# PGTN_daisy2_main_12cvin.net
KiCad netlist of a schematic drawn in EAGLE
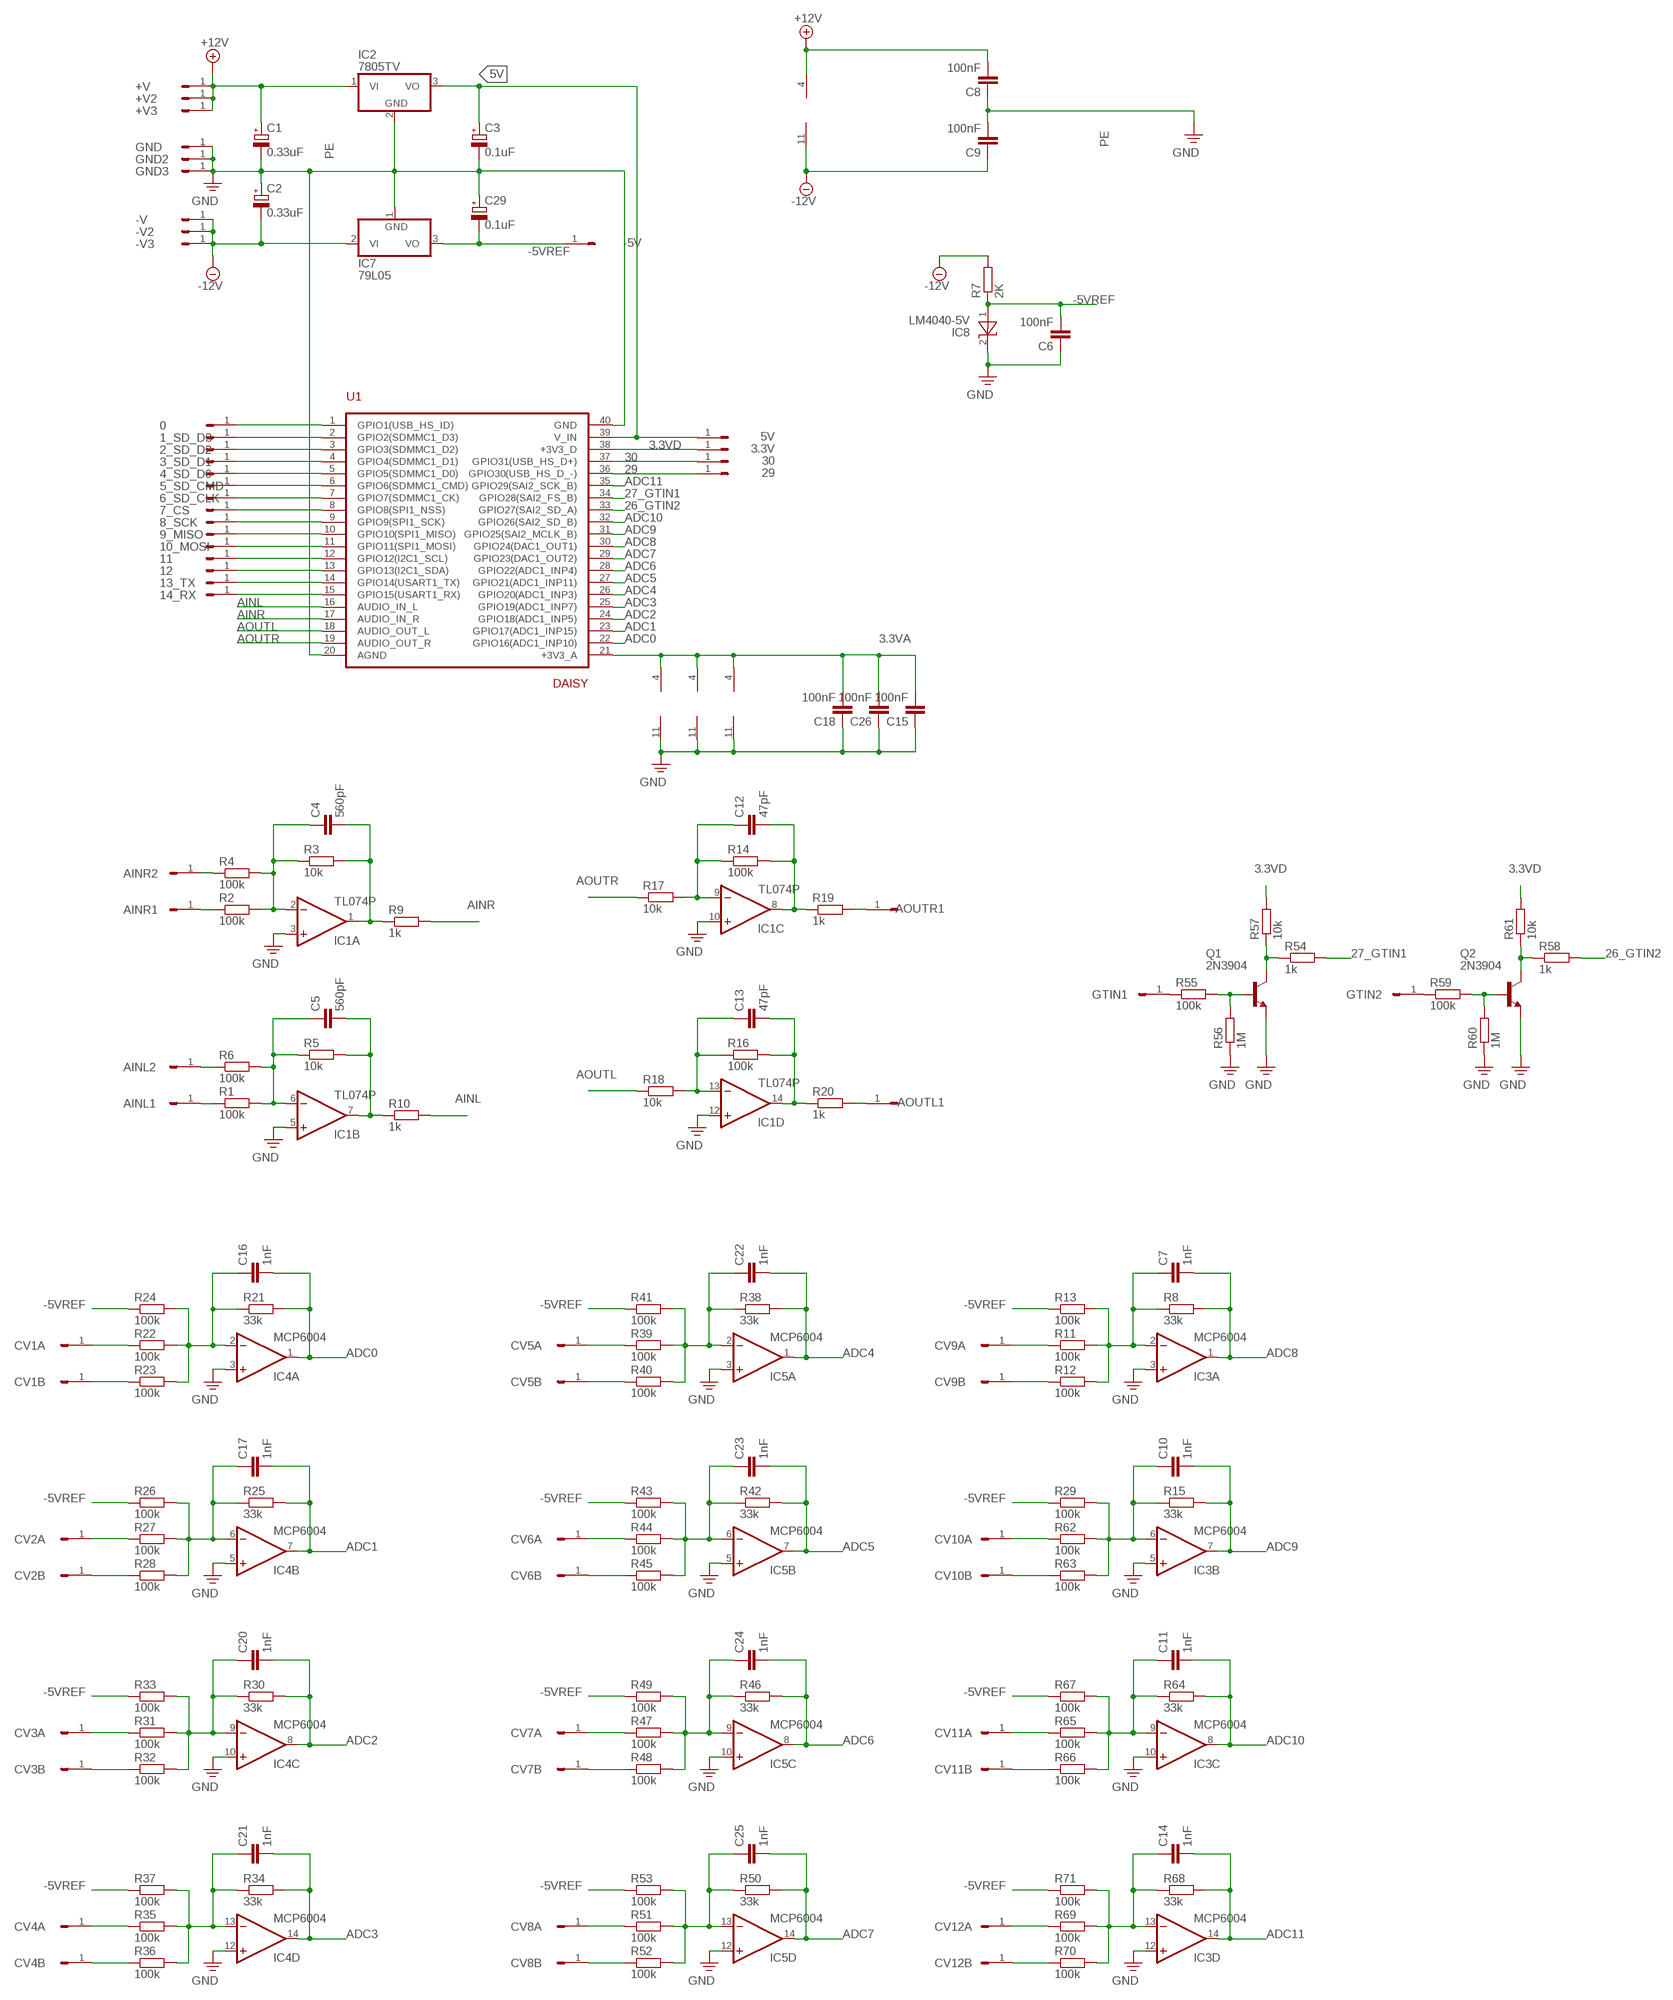
[diagram p0: schematic, sheet 1]

(export (version "E")
  (design (tool "Eeschema 10.0.6"))
  (components
    (comp (ref "+V")
      (value "HEADER/MALE/01")
      (footprint "eagle-import:HEADER_MALE_01")
      (fields (field (name "SPICEPREFIX") "X"))
      (libsource (lib "eagle-import") (part "HEADER/MALE/01"))
    )
    (comp (ref "+V2")
      (value "HEADER/MALE/01")
      (footprint "eagle-import:HEADER_MALE_01")
      (fields (field (name "SPICEPREFIX") "X"))
      (libsource (lib "eagle-import") (part "HEADER/MALE/01"))
    )
    (comp (ref "+V3")
      (value "HEADER/MALE/01")
      (footprint "eagle-import:HEADER_MALE_01")
      (fields (field (name "SPICEPREFIX") "X"))
      (libsource (lib "eagle-import") (part "HEADER/MALE/01"))
    )
    (comp (ref "-5V")
      (value "HEADER/MALE/01")
      (footprint "eagle-import:HEADER_MALE_01")
      (fields (field (name "SPICEPREFIX") "X"))
      (libsource (lib "eagle-import") (part "HEADER/MALE/01"))
    )
    (comp (ref "-V")
      (value "HEADER/MALE/01")
      (footprint "eagle-import:HEADER_MALE_01")
      (fields (field (name "SPICEPREFIX") "X"))
      (libsource (lib "eagle-import") (part "HEADER/MALE/01"))
    )
    (comp (ref "-V2")
      (value "HEADER/MALE/01")
      (footprint "eagle-import:HEADER_MALE_01")
      (fields (field (name "SPICEPREFIX") "X"))
      (libsource (lib "eagle-import") (part "HEADER/MALE/01"))
    )
    (comp (ref "-V3")
      (value "HEADER/MALE/01")
      (footprint "eagle-import:HEADER_MALE_01")
      (fields (field (name "SPICEPREFIX") "X"))
      (libsource (lib "eagle-import") (part "HEADER/MALE/01"))
    )
    (comp (ref "0")
      (value "HEADER/MALE/01")
      (footprint "eagle-import:HEADER_MALE_01")
      (fields (field (name "SPICEPREFIX") "X"))
      (libsource (lib "eagle-import") (part "HEADER/MALE/01"))
    )
    (comp (ref "1_SD_D3")
      (value "HEADER/MALE/01")
      (footprint "eagle-import:HEADER_MALE_01")
      (fields (field (name "SPICEPREFIX") "X"))
      (libsource (lib "eagle-import") (part "HEADER/MALE/01"))
    )
    (comp (ref "2_SD_D2")
      (value "HEADER/MALE/01")
      (footprint "eagle-import:HEADER_MALE_01")
      (fields (field (name "SPICEPREFIX") "X"))
      (libsource (lib "eagle-import") (part "HEADER/MALE/01"))
    )
    (comp (ref "3.3V")
      (value "HEADER/MALE/01")
      (footprint "eagle-import:HEADER_MALE_01")
      (fields (field (name "SPICEPREFIX") "X"))
      (libsource (lib "eagle-import") (part "HEADER/MALE/01"))
    )
    (comp (ref "3_SD_D1")
      (value "HEADER/MALE/01")
      (footprint "eagle-import:HEADER_MALE_01")
      (fields (field (name "SPICEPREFIX") "X"))
      (libsource (lib "eagle-import") (part "HEADER/MALE/01"))
    )
    (comp (ref "4_SD_D0")
      (value "HEADER/MALE/01")
      (footprint "eagle-import:HEADER_MALE_01")
      (fields (field (name "SPICEPREFIX") "X"))
      (libsource (lib "eagle-import") (part "HEADER/MALE/01"))
    )
    (comp (ref "5V")
      (value "HEADER/MALE/01")
      (footprint "eagle-import:HEADER_MALE_01")
      (fields (field (name "SPICEPREFIX") "X"))
      (libsource (lib "eagle-import") (part "HEADER/MALE/01"))
    )
    (comp (ref "5_SD_CMD")
      (value "HEADER/MALE/01")
      (footprint "eagle-import:HEADER_MALE_01")
      (fields (field (name "SPICEPREFIX") "X"))
      (libsource (lib "eagle-import") (part "HEADER/MALE/01"))
    )
    (comp (ref "6_SD_CLK")
      (value "HEADER/MALE/01")
      (footprint "eagle-import:HEADER_MALE_01")
      (fields (field (name "SPICEPREFIX") "X"))
      (libsource (lib "eagle-import") (part "HEADER/MALE/01"))
    )
    (comp (ref "7_CS")
      (value "HEADER/MALE/01")
      (footprint "eagle-import:HEADER_MALE_01")
      (fields (field (name "SPICEPREFIX") "X"))
      (libsource (lib "eagle-import") (part "HEADER/MALE/01"))
    )
    (comp (ref "8_SCK")
      (value "HEADER/MALE/01")
      (footprint "eagle-import:HEADER_MALE_01")
      (fields (field (name "SPICEPREFIX") "X"))
      (libsource (lib "eagle-import") (part "HEADER/MALE/01"))
    )
    (comp (ref "9_MISO")
      (value "HEADER/MALE/01")
      (footprint "eagle-import:HEADER_MALE_01")
      (fields (field (name "SPICEPREFIX") "X"))
      (libsource (lib "eagle-import") (part "HEADER/MALE/01"))
    )
    (comp (ref "10_MOSI")
      (value "HEADER/MALE/01")
      (footprint "eagle-import:HEADER_MALE_01")
      (fields (field (name "SPICEPREFIX") "X"))
      (libsource (lib "eagle-import") (part "HEADER/MALE/01"))
    )
    (comp (ref "11")
      (value "HEADER/MALE/01")
      (footprint "eagle-import:HEADER_MALE_01")
      (fields (field (name "SPICEPREFIX") "X"))
      (libsource (lib "eagle-import") (part "HEADER/MALE/01"))
    )
    (comp (ref "12")
      (value "HEADER/MALE/01")
      (footprint "eagle-import:HEADER_MALE_01")
      (fields (field (name "SPICEPREFIX") "X"))
      (libsource (lib "eagle-import") (part "HEADER/MALE/01"))
    )
    (comp (ref "13_TX")
      (value "HEADER/MALE/01")
      (footprint "eagle-import:HEADER_MALE_01")
      (fields (field (name "SPICEPREFIX") "X"))
      (libsource (lib "eagle-import") (part "HEADER/MALE/01"))
    )
    (comp (ref "14_RX")
      (value "HEADER/MALE/01")
      (footprint "eagle-import:HEADER_MALE_01")
      (fields (field (name "SPICEPREFIX") "X"))
      (libsource (lib "eagle-import") (part "HEADER/MALE/01"))
    )
    (comp (ref "29")
      (value "HEADER/MALE/01")
      (footprint "eagle-import:HEADER_MALE_01")
      (fields (field (name "SPICEPREFIX") "X"))
      (libsource (lib "eagle-import") (part "HEADER/MALE/01"))
    )
    (comp (ref "30")
      (value "HEADER/MALE/01")
      (footprint "eagle-import:HEADER_MALE_01")
      (fields (field (name "SPICEPREFIX") "X"))
      (libsource (lib "eagle-import") (part "HEADER/MALE/01"))
    )
    (comp (ref "AINL1")
      (value "HEADER/MALE/01")
      (footprint "eagle-import:HEADER_MALE_01")
      (fields (field (name "SPICEPREFIX") "X"))
      (libsource (lib "eagle-import") (part "HEADER/MALE/01"))
    )
    (comp (ref "AINL2")
      (value "HEADER/MALE/01")
      (footprint "eagle-import:HEADER_MALE_01")
      (fields (field (name "SPICEPREFIX") "X"))
      (libsource (lib "eagle-import") (part "HEADER/MALE/01"))
    )
    (comp (ref "AINR1")
      (value "HEADER/MALE/01")
      (footprint "eagle-import:HEADER_MALE_01")
      (fields (field (name "SPICEPREFIX") "X"))
      (libsource (lib "eagle-import") (part "HEADER/MALE/01"))
    )
    (comp (ref "AINR2")
      (value "HEADER/MALE/01")
      (footprint "eagle-import:HEADER_MALE_01")
      (fields (field (name "SPICEPREFIX") "X"))
      (libsource (lib "eagle-import") (part "HEADER/MALE/01"))
    )
    (comp (ref "AOUTL1")
      (value "HEADER/MALE/01")
      (footprint "eagle-import:HEADER_MALE_01")
      (fields (field (name "SPICEPREFIX") "X"))
      (libsource (lib "eagle-import") (part "HEADER/MALE/01"))
    )
    (comp (ref "AOUTR1")
      (value "HEADER/MALE/01")
      (footprint "eagle-import:HEADER_MALE_01")
      (fields (field (name "SPICEPREFIX") "X"))
      (libsource (lib "eagle-import") (part "HEADER/MALE/01"))
    )
    (comp (ref "C1")
      (value "0.33uF")
      (footprint "eagle-import:E2,5-6")
      (fields (field (name "SPICEPREFIX") "C"))
      (libsource (lib "eagle-import") (part "CAPACITOR/POLARIZEDE2.5-6"))
    )
    (comp (ref "C2")
      (value "0.33uF")
      (footprint "eagle-import:E2,5-6")
      (fields (field (name "SPICEPREFIX") "C"))
      (libsource (lib "eagle-import") (part "CAPACITOR/POLARIZEDE2.5-6"))
    )
    (comp (ref "C3")
      (value "0.1uF")
      (footprint "eagle-import:E2,5-6")
      (fields (field (name "SPICEPREFIX") "C"))
      (libsource (lib "eagle-import") (part "CAPACITOR/POLARIZEDE2.5-6"))
    )
    (comp (ref "C4")
      (value "560pF")
      (footprint "eagle-import:CERAMICDISC_5")
      (libsource (lib "eagle-import") (part "CAPACITORCERAMICDISC/5"))
    )
    (comp (ref "C5")
      (value "560pF")
      (footprint "eagle-import:CERAMICDISC_5")
      (libsource (lib "eagle-import") (part "CAPACITORCERAMICDISC/5"))
    )
    (comp (ref "C6")
      (value "100nF")
      (footprint "eagle-import:CERAMICDISC_5")
      (libsource (lib "eagle-import") (part "CAPACITORCERAMICDISC/5"))
    )
    (comp (ref "C7")
      (value "1nF")
      (footprint "eagle-import:CERAMICDISC_5")
      (libsource (lib "eagle-import") (part "CAPACITORCERAMICDISC/5"))
    )
    (comp (ref "C8")
      (value "100nF")
      (footprint "eagle-import:CERAMICDISC_5")
      (libsource (lib "eagle-import") (part "CAPACITORCERAMICDISC/5"))
    )
    (comp (ref "C9")
      (value "100nF")
      (footprint "eagle-import:CERAMICDISC_5")
      (libsource (lib "eagle-import") (part "CAPACITORCERAMICDISC/5"))
    )
    (comp (ref "C10")
      (value "1nF")
      (footprint "eagle-import:CERAMICDISC_5")
      (libsource (lib "eagle-import") (part "CAPACITORCERAMICDISC/5"))
    )
    (comp (ref "C11")
      (value "1nF")
      (footprint "eagle-import:CERAMICDISC_5")
      (libsource (lib "eagle-import") (part "CAPACITORCERAMICDISC/5"))
    )
    (comp (ref "C12")
      (value "47pF")
      (footprint "eagle-import:CERAMICDISC_5")
      (libsource (lib "eagle-import") (part "CAPACITORCERAMICDISC/5"))
    )
    (comp (ref "C13")
      (value "47pF")
      (footprint "eagle-import:CERAMICDISC_5")
      (libsource (lib "eagle-import") (part "CAPACITORCERAMICDISC/5"))
    )
    (comp (ref "C14")
      (value "1nF")
      (footprint "eagle-import:CERAMICDISC_5")
      (libsource (lib "eagle-import") (part "CAPACITORCERAMICDISC/5"))
    )
    (comp (ref "C15")
      (value "100nF")
      (footprint "eagle-import:CERAMICDISC_5")
      (libsource (lib "eagle-import") (part "CAPACITORCERAMICDISC/5"))
    )
    (comp (ref "C16")
      (value "1nF")
      (footprint "eagle-import:CERAMICDISC_5")
      (libsource (lib "eagle-import") (part "CAPACITORCERAMICDISC/5"))
    )
    (comp (ref "C17")
      (value "1nF")
      (footprint "eagle-import:CERAMICDISC_5")
      (libsource (lib "eagle-import") (part "CAPACITORCERAMICDISC/5"))
    )
    (comp (ref "C18")
      (value "100nF")
      (footprint "eagle-import:CERAMICDISC_5")
      (libsource (lib "eagle-import") (part "CAPACITORCERAMICDISC/5"))
    )
    (comp (ref "C20")
      (value "1nF")
      (footprint "eagle-import:CERAMICDISC_5")
      (libsource (lib "eagle-import") (part "CAPACITORCERAMICDISC/5"))
    )
    (comp (ref "C21")
      (value "1nF")
      (footprint "eagle-import:CERAMICDISC_5")
      (libsource (lib "eagle-import") (part "CAPACITORCERAMICDISC/5"))
    )
    (comp (ref "C22")
      (value "1nF")
      (footprint "eagle-import:CERAMICDISC_5")
      (libsource (lib "eagle-import") (part "CAPACITORCERAMICDISC/5"))
    )
    (comp (ref "C23")
      (value "1nF")
      (footprint "eagle-import:CERAMICDISC_5")
      (libsource (lib "eagle-import") (part "CAPACITORCERAMICDISC/5"))
    )
    (comp (ref "C24")
      (value "1nF")
      (footprint "eagle-import:CERAMICDISC_5")
      (libsource (lib "eagle-import") (part "CAPACITORCERAMICDISC/5"))
    )
    (comp (ref "C25")
      (value "1nF")
      (footprint "eagle-import:CERAMICDISC_5")
      (libsource (lib "eagle-import") (part "CAPACITORCERAMICDISC/5"))
    )
    (comp (ref "C26")
      (value "100nF")
      (footprint "eagle-import:CERAMICDISC_5")
      (libsource (lib "eagle-import") (part "CAPACITORCERAMICDISC/5"))
    )
    (comp (ref "C29")
      (value "0.1uF")
      (footprint "eagle-import:E2,5-6")
      (fields (field (name "SPICEPREFIX") "C"))
      (libsource (lib "eagle-import") (part "CAPACITOR/POLARIZEDE2.5-6"))
    )
    (comp (ref "CV1A")
      (value "HEADER/MALE/01")
      (footprint "eagle-import:HEADER_MALE_01")
      (fields (field (name "SPICEPREFIX") "X"))
      (libsource (lib "eagle-import") (part "HEADER/MALE/01"))
    )
    (comp (ref "CV1B")
      (value "HEADER/MALE/01")
      (footprint "eagle-import:HEADER_MALE_01")
      (fields (field (name "SPICEPREFIX") "X"))
      (libsource (lib "eagle-import") (part "HEADER/MALE/01"))
    )
    (comp (ref "CV2A")
      (value "HEADER/MALE/01")
      (footprint "eagle-import:HEADER_MALE_01")
      (fields (field (name "SPICEPREFIX") "X"))
      (libsource (lib "eagle-import") (part "HEADER/MALE/01"))
    )
    (comp (ref "CV2B")
      (value "HEADER/MALE/01")
      (footprint "eagle-import:HEADER_MALE_01")
      (fields (field (name "SPICEPREFIX") "X"))
      (libsource (lib "eagle-import") (part "HEADER/MALE/01"))
    )
    (comp (ref "CV3A")
      (value "HEADER/MALE/01")
      (footprint "eagle-import:HEADER_MALE_01")
      (fields (field (name "SPICEPREFIX") "X"))
      (libsource (lib "eagle-import") (part "HEADER/MALE/01"))
    )
    (comp (ref "CV3B")
      (value "HEADER/MALE/01")
      (footprint "eagle-import:HEADER_MALE_01")
      (fields (field (name "SPICEPREFIX") "X"))
      (libsource (lib "eagle-import") (part "HEADER/MALE/01"))
    )
    (comp (ref "CV4A")
      (value "HEADER/MALE/01")
      (footprint "eagle-import:HEADER_MALE_01")
      (fields (field (name "SPICEPREFIX") "X"))
      (libsource (lib "eagle-import") (part "HEADER/MALE/01"))
    )
    (comp (ref "CV4B")
      (value "HEADER/MALE/01")
      (footprint "eagle-import:HEADER_MALE_01")
      (fields (field (name "SPICEPREFIX") "X"))
      (libsource (lib "eagle-import") (part "HEADER/MALE/01"))
    )
    (comp (ref "CV5A")
      (value "HEADER/MALE/01")
      (footprint "eagle-import:HEADER_MALE_01")
      (fields (field (name "SPICEPREFIX") "X"))
      (libsource (lib "eagle-import") (part "HEADER/MALE/01"))
    )
    (comp (ref "CV5B")
      (value "HEADER/MALE/01")
      (footprint "eagle-import:HEADER_MALE_01")
      (fields (field (name "SPICEPREFIX") "X"))
      (libsource (lib "eagle-import") (part "HEADER/MALE/01"))
    )
    (comp (ref "CV6A")
      (value "HEADER/MALE/01")
      (footprint "eagle-import:HEADER_MALE_01")
      (fields (field (name "SPICEPREFIX") "X"))
      (libsource (lib "eagle-import") (part "HEADER/MALE/01"))
    )
    (comp (ref "CV6B")
      (value "HEADER/MALE/01")
      (footprint "eagle-import:HEADER_MALE_01")
      (fields (field (name "SPICEPREFIX") "X"))
      (libsource (lib "eagle-import") (part "HEADER/MALE/01"))
    )
    (comp (ref "CV7A")
      (value "HEADER/MALE/01")
      (footprint "eagle-import:HEADER_MALE_01")
      (fields (field (name "SPICEPREFIX") "X"))
      (libsource (lib "eagle-import") (part "HEADER/MALE/01"))
    )
    (comp (ref "CV7B")
      (value "HEADER/MALE/01")
      (footprint "eagle-import:HEADER_MALE_01")
      (fields (field (name "SPICEPREFIX") "X"))
      (libsource (lib "eagle-import") (part "HEADER/MALE/01"))
    )
    (comp (ref "CV8A")
      (value "HEADER/MALE/01")
      (footprint "eagle-import:HEADER_MALE_01")
      (fields (field (name "SPICEPREFIX") "X"))
      (libsource (lib "eagle-import") (part "HEADER/MALE/01"))
    )
    (comp (ref "CV8B")
      (value "HEADER/MALE/01")
      (footprint "eagle-import:HEADER_MALE_01")
      (fields (field (name "SPICEPREFIX") "X"))
      (libsource (lib "eagle-import") (part "HEADER/MALE/01"))
    )
    (comp (ref "CV9A")
      (value "HEADER/MALE/01")
      (footprint "eagle-import:HEADER_MALE_01")
      (fields (field (name "SPICEPREFIX") "X"))
      (libsource (lib "eagle-import") (part "HEADER/MALE/01"))
    )
    (comp (ref "CV9B")
      (value "HEADER/MALE/01")
      (footprint "eagle-import:HEADER_MALE_01")
      (fields (field (name "SPICEPREFIX") "X"))
      (libsource (lib "eagle-import") (part "HEADER/MALE/01"))
    )
    (comp (ref "CV10A")
      (value "HEADER/MALE/01")
      (footprint "eagle-import:HEADER_MALE_01")
      (fields (field (name "SPICEPREFIX") "X"))
      (libsource (lib "eagle-import") (part "HEADER/MALE/01"))
    )
    (comp (ref "CV10B")
      (value "HEADER/MALE/01")
      (footprint "eagle-import:HEADER_MALE_01")
      (fields (field (name "SPICEPREFIX") "X"))
      (libsource (lib "eagle-import") (part "HEADER/MALE/01"))
    )
    (comp (ref "CV11A")
      (value "HEADER/MALE/01")
      (footprint "eagle-import:HEADER_MALE_01")
      (fields (field (name "SPICEPREFIX") "X"))
      (libsource (lib "eagle-import") (part "HEADER/MALE/01"))
    )
    (comp (ref "CV11B")
      (value "HEADER/MALE/01")
      (footprint "eagle-import:HEADER_MALE_01")
      (fields (field (name "SPICEPREFIX") "X"))
      (libsource (lib "eagle-import") (part "HEADER/MALE/01"))
    )
    (comp (ref "CV12A")
      (value "HEADER/MALE/01")
      (footprint "eagle-import:HEADER_MALE_01")
      (fields (field (name "SPICEPREFIX") "X"))
      (libsource (lib "eagle-import") (part "HEADER/MALE/01"))
    )
    (comp (ref "CV12B")
      (value "HEADER/MALE/01")
      (footprint "eagle-import:HEADER_MALE_01")
      (fields (field (name "SPICEPREFIX") "X"))
      (libsource (lib "eagle-import") (part "HEADER/MALE/01"))
    )
    (comp (ref "GND")
      (value "HEADER/MALE/01")
      (footprint "eagle-import:HEADER_MALE_01")
      (fields (field (name "SPICEPREFIX") "X"))
      (libsource (lib "eagle-import") (part "HEADER/MALE/01"))
    )
    (comp (ref "GND2")
      (value "HEADER/MALE/01")
      (footprint "eagle-import:HEADER_MALE_01")
      (fields (field (name "SPICEPREFIX") "X"))
      (libsource (lib "eagle-import") (part "HEADER/MALE/01"))
    )
    (comp (ref "GND3")
      (value "HEADER/MALE/01")
      (footprint "eagle-import:HEADER_MALE_01")
      (fields (field (name "SPICEPREFIX") "X"))
      (libsource (lib "eagle-import") (part "HEADER/MALE/01"))
    )
    (comp (ref "GTIN1")
      (value "HEADER/MALE/01")
      (footprint "eagle-import:HEADER_MALE_01")
      (fields (field (name "SPICEPREFIX") "X"))
      (libsource (lib "eagle-import") (part "HEADER/MALE/01"))
    )
    (comp (ref "GTIN2")
      (value "HEADER/MALE/01")
      (footprint "eagle-import:HEADER_MALE_01")
      (fields (field (name "SPICEPREFIX") "X"))
      (libsource (lib "eagle-import") (part "HEADER/MALE/01"))
    )
    (comp (ref "IC1")
      (value "TL074P")
      (footprint "eagle-import:DIL14")
      (libsource (lib "eagle-import") (part "TL074P"))
    )
    (comp (ref "IC2")
      (value "7805TV")
      (footprint "eagle-import:TO220V")
      (libsource (lib "eagle-import") (part "78TV05"))
    )
    (comp (ref "IC3")
      (value "MCP6004")
      (footprint "eagle-import:DIL14")
      (libsource (lib "eagle-import") (part "TL074P"))
    )
    (comp (ref "IC4")
      (value "MCP6004")
      (footprint "eagle-import:DIL14")
      (libsource (lib "eagle-import") (part "TL074P"))
    )
    (comp (ref "IC5")
      (value "MCP6004")
      (footprint "eagle-import:DIL14")
      (libsource (lib "eagle-import") (part "TL074P"))
    )
    (comp (ref "IC7")
      (value "79L05")
      (footprint "eagle-import:TO92")
      (libsource (lib "eagle-import") (part "79ZL05"))
    )
    (comp (ref "IC8")
      (value "LM4040-5V")
      (footprint "eagle-import:TO92")
      (libsource (lib "eagle-import") (part "LM4040"))
    )
    (comp (ref "Q1")
      (value "2N3904")
      (footprint "eagle-import:TO92")
      (libsource (lib "eagle-import") (part "2N3904"))
    )
    (comp (ref "Q2")
      (value "2N3904")
      (footprint "eagle-import:TO92")
      (libsource (lib "eagle-import") (part "2N3904"))
    )
    (comp (ref "R1")
      (value "100k")
      (footprint "eagle-import:RESISTOR_7.5")
      (libsource (lib "eagle-import") (part "RESISTORRESISTOR/UPRIGHT/7.5"))
    )
    (comp (ref "R2")
      (value "100k")
      (footprint "eagle-import:RESISTOR_7.5")
      (libsource (lib "eagle-import") (part "RESISTORRESISTOR/UPRIGHT/7.5"))
    )
    (comp (ref "R3")
      (value "10k")
      (footprint "eagle-import:RESISTOR_7.5")
      (libsource (lib "eagle-import") (part "RESISTORRESISTOR/UPRIGHT/7.5"))
    )
    (comp (ref "R4")
      (value "100k")
      (footprint "eagle-import:RESISTOR_7.5")
      (libsource (lib "eagle-import") (part "RESISTORRESISTOR/UPRIGHT/7.5"))
    )
    (comp (ref "R5")
      (value "10k")
      (footprint "eagle-import:RESISTOR_7.5")
      (libsource (lib "eagle-import") (part "RESISTORRESISTOR/UPRIGHT/7.5"))
    )
    (comp (ref "R6")
      (value "100k")
      (footprint "eagle-import:RESISTOR_7.5")
      (libsource (lib "eagle-import") (part "RESISTORRESISTOR/UPRIGHT/7.5"))
    )
    (comp (ref "R7")
      (value "2K")
      (footprint "eagle-import:RESISTOR_7.5")
      (libsource (lib "eagle-import") (part "RESISTORRESISTOR/UPRIGHT/7.5"))
    )
    (comp (ref "R8")
      (value "33k")
      (footprint "eagle-import:RESISTOR_7.5")
      (libsource (lib "eagle-import") (part "RESISTORRESISTOR/UPRIGHT/7.5"))
    )
    (comp (ref "R9")
      (value "1k")
      (footprint "eagle-import:RESISTOR_7.5")
      (libsource (lib "eagle-import") (part "RESISTORRESISTOR/UPRIGHT/7.5"))
    )
    (comp (ref "R10")
      (value "1k")
      (footprint "eagle-import:RESISTOR_7.5")
      (libsource (lib "eagle-import") (part "RESISTORRESISTOR/UPRIGHT/7.5"))
    )
    (comp (ref "R11")
      (value "100k")
      (footprint "eagle-import:RESISTOR_7.5")
      (libsource (lib "eagle-import") (part "RESISTORRESISTOR/UPRIGHT/7.5"))
    )
    (comp (ref "R12")
      (value "100k")
      (footprint "eagle-import:RESISTOR_7.5")
      (libsource (lib "eagle-import") (part "RESISTORRESISTOR/UPRIGHT/7.5"))
    )
    (comp (ref "R13")
      (value "100k")
      (footprint "eagle-import:RESISTOR_7.5")
      (libsource (lib "eagle-import") (part "RESISTORRESISTOR/UPRIGHT/7.5"))
    )
    (comp (ref "R14")
      (value "100k")
      (footprint "eagle-import:RESISTOR_7.5")
      (libsource (lib "eagle-import") (part "RESISTORRESISTOR/UPRIGHT/7.5"))
    )
    (comp (ref "R15")
      (value "33k")
      (footprint "eagle-import:RESISTOR_7.5")
      (libsource (lib "eagle-import") (part "RESISTORRESISTOR/UPRIGHT/7.5"))
    )
    (comp (ref "R16")
      (value "100k")
      (footprint "eagle-import:RESISTOR_7.5")
      (libsource (lib "eagle-import") (part "RESISTORRESISTOR/UPRIGHT/7.5"))
    )
    (comp (ref "R17")
      (value "10k")
      (footprint "eagle-import:RESISTOR_7.5")
      (libsource (lib "eagle-import") (part "RESISTORRESISTOR/UPRIGHT/7.5"))
    )
    (comp (ref "R18")
      (value "10k")
      (footprint "eagle-import:RESISTOR_7.5")
      (libsource (lib "eagle-import") (part "RESISTORRESISTOR/UPRIGHT/7.5"))
    )
    (comp (ref "R19")
      (value "1k")
      (footprint "eagle-import:RESISTOR_7.5")
      (libsource (lib "eagle-import") (part "RESISTORRESISTOR/UPRIGHT/7.5"))
    )
    (comp (ref "R20")
      (value "1k")
      (footprint "eagle-import:RESISTOR_7.5")
      (libsource (lib "eagle-import") (part "RESISTORRESISTOR/UPRIGHT/7.5"))
    )
    (comp (ref "R21")
      (value "33k")
      (footprint "eagle-import:RESISTOR_7.5")
      (libsource (lib "eagle-import") (part "RESISTORRESISTOR/UPRIGHT/7.5"))
    )
    (comp (ref "R22")
      (value "100k")
      (footprint "eagle-import:RESISTOR_7.5")
      (libsource (lib "eagle-import") (part "RESISTORRESISTOR/UPRIGHT/7.5"))
    )
    (comp (ref "R23")
      (value "100k")
      (footprint "eagle-import:RESISTOR_7.5")
      (libsource (lib "eagle-import") (part "RESISTORRESISTOR/UPRIGHT/7.5"))
    )
    (comp (ref "R24")
      (value "100k")
      (footprint "eagle-import:RESISTOR_7.5")
      (libsource (lib "eagle-import") (part "RESISTORRESISTOR/UPRIGHT/7.5"))
    )
    (comp (ref "R25")
      (value "33k")
      (footprint "eagle-import:RESISTOR_7.5")
      (libsource (lib "eagle-import") (part "RESISTORRESISTOR/UPRIGHT/7.5"))
    )
    (comp (ref "R26")
      (value "100k")
      (footprint "eagle-import:RESISTOR_7.5")
      (libsource (lib "eagle-import") (part "RESISTORRESISTOR/UPRIGHT/7.5"))
    )
    (comp (ref "R27")
      (value "100k")
      (footprint "eagle-import:RESISTOR_7.5")
      (libsource (lib "eagle-import") (part "RESISTORRESISTOR/UPRIGHT/7.5"))
    )
    (comp (ref "R28")
      (value "100k")
      (footprint "eagle-import:RESISTOR_7.5")
      (libsource (lib "eagle-import") (part "RESISTORRESISTOR/UPRIGHT/7.5"))
    )
    (comp (ref "R29")
      (value "100k")
      (footprint "eagle-import:RESISTOR_7.5")
      (libsource (lib "eagle-import") (part "RESISTORRESISTOR/UPRIGHT/7.5"))
    )
    (comp (ref "R30")
      (value "33k")
      (footprint "eagle-import:RESISTOR_7.5")
      (libsource (lib "eagle-import") (part "RESISTORRESISTOR/UPRIGHT/7.5"))
    )
    (comp (ref "R31")
      (value "100k")
      (footprint "eagle-import:RESISTOR_7.5")
      (libsource (lib "eagle-import") (part "RESISTORRESISTOR/UPRIGHT/7.5"))
    )
    (comp (ref "R32")
      (value "100k")
      (footprint "eagle-import:RESISTOR_7.5")
      (libsource (lib "eagle-import") (part "RESISTORRESISTOR/UPRIGHT/7.5"))
    )
    (comp (ref "R33")
      (value "100k")
      (footprint "eagle-import:RESISTOR_7.5")
      (libsource (lib "eagle-import") (part "RESISTORRESISTOR/UPRIGHT/7.5"))
    )
    (comp (ref "R34")
      (value "33k")
      (footprint "eagle-import:RESISTOR_7.5")
      (libsource (lib "eagle-import") (part "RESISTORRESISTOR/UPRIGHT/7.5"))
    )
    (comp (ref "R35")
      (value "100k")
      (footprint "eagle-import:RESISTOR_7.5")
      (libsource (lib "eagle-import") (part "RESISTORRESISTOR/UPRIGHT/7.5"))
    )
    (comp (ref "R36")
      (value "100k")
      (footprint "eagle-import:RESISTOR_7.5")
      (libsource (lib "eagle-import") (part "RESISTORRESISTOR/UPRIGHT/7.5"))
    )
    (comp (ref "R37")
      (value "100k")
      (footprint "eagle-import:RESISTOR_7.5")
      (libsource (lib "eagle-import") (part "RESISTORRESISTOR/UPRIGHT/7.5"))
    )
    (comp (ref "R38")
      (value "33k")
      (footprint "eagle-import:RESISTOR_7.5")
      (libsource (lib "eagle-import") (part "RESISTORRESISTOR/UPRIGHT/7.5"))
    )
    (comp (ref "R39")
      (value "100k")
      (footprint "eagle-import:RESISTOR_7.5")
      (libsource (lib "eagle-import") (part "RESISTORRESISTOR/UPRIGHT/7.5"))
    )
    (comp (ref "R40")
      (value "100k")
      (footprint "eagle-import:RESISTOR_7.5")
      (libsource (lib "eagle-import") (part "RESISTORRESISTOR/UPRIGHT/7.5"))
    )
    (comp (ref "R41")
      (value "100k")
      (footprint "eagle-import:RESISTOR_7.5")
      (libsource (lib "eagle-import") (part "RESISTORRESISTOR/UPRIGHT/7.5"))
    )
    (comp (ref "R42")
      (value "33k")
      (footprint "eagle-import:RESISTOR_7.5")
      (libsource (lib "eagle-import") (part "RESISTORRESISTOR/UPRIGHT/7.5"))
    )
    (comp (ref "R43")
      (value "100k")
      (footprint "eagle-import:RESISTOR_7.5")
      (libsource (lib "eagle-import") (part "RESISTORRESISTOR/UPRIGHT/7.5"))
    )
    (comp (ref "R44")
      (value "100k")
      (footprint "eagle-import:RESISTOR_7.5")
      (libsource (lib "eagle-import") (part "RESISTORRESISTOR/UPRIGHT/7.5"))
    )
    (comp (ref "R45")
      (value "100k")
      (footprint "eagle-import:RESISTOR_7.5")
      (libsource (lib "eagle-import") (part "RESISTORRESISTOR/UPRIGHT/7.5"))
    )
    (comp (ref "R46")
      (value "33k")
      (footprint "eagle-import:RESISTOR_7.5")
      (libsource (lib "eagle-import") (part "RESISTORRESISTOR/UPRIGHT/7.5"))
    )
    (comp (ref "R47")
      (value "100k")
      (footprint "eagle-import:RESISTOR_7.5")
      (libsource (lib "eagle-import") (part "RESISTORRESISTOR/UPRIGHT/7.5"))
    )
    (comp (ref "R48")
      (value "100k")
      (footprint "eagle-import:RESISTOR_7.5")
      (libsource (lib "eagle-import") (part "RESISTORRESISTOR/UPRIGHT/7.5"))
    )
    (comp (ref "R49")
      (value "100k")
      (footprint "eagle-import:RESISTOR_7.5")
      (libsource (lib "eagle-import") (part "RESISTORRESISTOR/UPRIGHT/7.5"))
    )
    (comp (ref "R50")
      (value "33k")
      (footprint "eagle-import:RESISTOR_7.5")
      (libsource (lib "eagle-import") (part "RESISTORRESISTOR/UPRIGHT/7.5"))
    )
    (comp (ref "R51")
      (value "100k")
      (footprint "eagle-import:RESISTOR_7.5")
      (libsource (lib "eagle-import") (part "RESISTORRESISTOR/UPRIGHT/7.5"))
    )
    (comp (ref "R52")
      (value "100k")
      (footprint "eagle-import:RESISTOR_7.5")
      (libsource (lib "eagle-import") (part "RESISTORRESISTOR/UPRIGHT/7.5"))
    )
    (comp (ref "R53")
      (value "100k")
      (footprint "eagle-import:RESISTOR_7.5")
      (libsource (lib "eagle-import") (part "RESISTORRESISTOR/UPRIGHT/7.5"))
    )
    (comp (ref "R54")
      (value "1k")
      (footprint "eagle-import:RESISTOR_7.5")
      (libsource (lib "eagle-import") (part "RESISTORRESISTOR/UPRIGHT/7.5"))
    )
    (comp (ref "R55")
      (value "100k")
      (footprint "eagle-import:RESISTOR_7.5")
      (libsource (lib "eagle-import") (part "RESISTORRESISTOR/UPRIGHT/7.5"))
    )
    (comp (ref "R56")
      (value "1M")
      (footprint "eagle-import:RESISTOR_7.5")
      (libsource (lib "eagle-import") (part "RESISTORRESISTOR/UPRIGHT/7.5"))
    )
    (comp (ref "R57")
      (value "10k")
      (footprint "eagle-import:RESISTOR_7.5")
      (libsource (lib "eagle-import") (part "RESISTORRESISTOR/UPRIGHT/7.5"))
    )
    (comp (ref "R58")
      (value "1k")
      (footprint "eagle-import:RESISTOR_7.5")
      (libsource (lib "eagle-import") (part "RESISTORRESISTOR/UPRIGHT/7.5"))
    )
    (comp (ref "R59")
      (value "100k")
      (footprint "eagle-import:RESISTOR_7.5")
      (libsource (lib "eagle-import") (part "RESISTORRESISTOR/UPRIGHT/7.5"))
    )
    (comp (ref "R60")
      (value "1M")
      (footprint "eagle-import:RESISTOR_7.5")
      (libsource (lib "eagle-import") (part "RESISTORRESISTOR/UPRIGHT/7.5"))
    )
    (comp (ref "R61")
      (value "10k")
      (footprint "eagle-import:RESISTOR_7.5")
      (libsource (lib "eagle-import") (part "RESISTORRESISTOR/UPRIGHT/7.5"))
    )
    (comp (ref "R62")
      (value "100k")
      (footprint "eagle-import:RESISTOR_7.5")
      (libsource (lib "eagle-import") (part "RESISTORRESISTOR/UPRIGHT/7.5"))
    )
    (comp (ref "R63")
      (value "100k")
      (footprint "eagle-import:RESISTOR_7.5")
      (libsource (lib "eagle-import") (part "RESISTORRESISTOR/UPRIGHT/7.5"))
    )
    (comp (ref "R64")
      (value "33k")
      (footprint "eagle-import:RESISTOR_7.5")
      (libsource (lib "eagle-import") (part "RESISTORRESISTOR/UPRIGHT/7.5"))
    )
    (comp (ref "R65")
      (value "100k")
      (footprint "eagle-import:RESISTOR_7.5")
      (libsource (lib "eagle-import") (part "RESISTORRESISTOR/UPRIGHT/7.5"))
    )
    (comp (ref "R66")
      (value "100k")
      (footprint "eagle-import:RESISTOR_7.5")
      (libsource (lib "eagle-import") (part "RESISTORRESISTOR/UPRIGHT/7.5"))
    )
    (comp (ref "R67")
      (value "100k")
      (footprint "eagle-import:RESISTOR_7.5")
      (libsource (lib "eagle-import") (part "RESISTORRESISTOR/UPRIGHT/7.5"))
    )
    (comp (ref "R68")
      (value "33k")
      (footprint "eagle-import:RESISTOR_7.5")
      (libsource (lib "eagle-import") (part "RESISTORRESISTOR/UPRIGHT/7.5"))
    )
    (comp (ref "R69")
      (value "100k")
      (footprint "eagle-import:RESISTOR_7.5")
      (libsource (lib "eagle-import") (part "RESISTORRESISTOR/UPRIGHT/7.5"))
    )
    (comp (ref "R70")
      (value "100k")
      (footprint "eagle-import:RESISTOR_7.5")
      (libsource (lib "eagle-import") (part "RESISTORRESISTOR/UPRIGHT/7.5"))
    )
    (comp (ref "R71")
      (value "100k")
      (footprint "eagle-import:RESISTOR_7.5")
      (libsource (lib "eagle-import") (part "RESISTORRESISTOR/UPRIGHT/7.5"))
    )
    (comp (ref "U1")
      (value "DAISY")
      (footprint "eagle-import:ES_DAISY_SEED")
      (libsource (lib "eagle-import") (part "ES_DAISY_SEED_REV4"))
    )
  )
  (nets
    (net (code "1") (name "+12V") (class "Default")
      (node (ref "+V") (pin "1") (pinfunction "3_1") (pintype "passive"))
      (node (ref "+V2") (pin "1") (pinfunction "3_1") (pintype "passive"))
      (node (ref "+V3") (pin "1") (pinfunction "3_1") (pintype "passive"))
      (node (ref "C1") (pin "+") (pinfunction "+_+") (pintype "passive"))
      (node (ref "C8") (pin "2") (pinfunction "2_2") (pintype "passive"))
      (node (ref "IC1") (pin "4") (pinfunction "V+_4") (pintype "power_in"))
      (node (ref "IC2") (pin "1") (pinfunction "VI_1") (pintype "input"))
    )
    (net (code "2") (name "-12V") (class "Default")
      (node (ref "-V") (pin "1") (pinfunction "3_1") (pintype "passive"))
      (node (ref "-V2") (pin "1") (pinfunction "3_1") (pintype "passive"))
      (node (ref "-V3") (pin "1") (pinfunction "3_1") (pintype "passive"))
      (node (ref "C2") (pin "-") (pinfunction "-_-") (pintype "passive"))
      (node (ref "C9") (pin "1") (pinfunction "1_1") (pintype "passive"))
      (node (ref "IC1") (pin "11") (pinfunction "V-_11") (pintype "power_in"))
      (node (ref "IC7") (pin "2") (pinfunction "VI_2") (pintype "input"))
      (node (ref "R7") (pin "2") (pinfunction "2_2") (pintype "passive"))
    )
    (net (code "3") (name "/-5VREF") (class "Default")
      (node (ref "-5V") (pin "1") (pinfunction "3_1") (pintype "passive"))
      (node (ref "C29") (pin "-") (pinfunction "-_-") (pintype "passive"))
      (node (ref "C6") (pin "2") (pinfunction "2_2") (pintype "passive"))
      (node (ref "IC7") (pin "3") (pinfunction "VO_3") (pintype "passive"))
      (node (ref "IC8") (pin "1") (pinfunction "A_1") (pintype "output"))
      (node (ref "R13") (pin "1") (pinfunction "1_1") (pintype "passive"))
      (node (ref "R24") (pin "1") (pinfunction "1_1") (pintype "passive"))
      (node (ref "R26") (pin "1") (pinfunction "1_1") (pintype "passive"))
      (node (ref "R29") (pin "1") (pinfunction "1_1") (pintype "passive"))
      (node (ref "R33") (pin "1") (pinfunction "1_1") (pintype "passive"))
      (node (ref "R37") (pin "1") (pinfunction "1_1") (pintype "passive"))
      (node (ref "R41") (pin "1") (pinfunction "1_1") (pintype "passive"))
      (node (ref "R43") (pin "1") (pinfunction "1_1") (pintype "passive"))
      (node (ref "R49") (pin "1") (pinfunction "1_1") (pintype "passive"))
      (node (ref "R53") (pin "1") (pinfunction "1_1") (pintype "passive"))
      (node (ref "R67") (pin "1") (pinfunction "1_1") (pintype "passive"))
      (node (ref "R7") (pin "1") (pinfunction "1_1") (pintype "passive"))
      (node (ref "R71") (pin "1") (pinfunction "1_1") (pintype "passive"))
    )
    (net (code "4") (name "/3.3VA") (class "Default")
      (node (ref "C15") (pin "2") (pinfunction "2_2") (pintype "passive"))
      (node (ref "C18") (pin "2") (pinfunction "2_2") (pintype "passive"))
      (node (ref "C26") (pin "2") (pinfunction "2_2") (pintype "passive"))
      (node (ref "IC3") (pin "4") (pinfunction "V+_4") (pintype "power_in"))
      (node (ref "IC4") (pin "4") (pinfunction "V+_4") (pintype "power_in"))
      (node (ref "IC5") (pin "4") (pinfunction "V+_4") (pintype "power_in"))
      (node (ref "U1") (pin "21") (pinfunction "+3V3_A_21") (pintype "bidirectional"))
    )
    (net (code "5") (name "/3.3VD") (class "Default")
      (node (ref "3.3V") (pin "1") (pinfunction "3_1") (pintype "passive"))
      (node (ref "R57") (pin "2") (pinfunction "2_2") (pintype "passive"))
      (node (ref "R61") (pin "2") (pinfunction "2_2") (pintype "passive"))
      (node (ref "U1") (pin "38") (pinfunction "+3V3_D_38") (pintype "bidirectional"))
    )
    (net (code "6") (name "/26_GTIN2") (class "Default")
      (node (ref "R58") (pin "2") (pinfunction "2_2") (pintype "passive"))
      (node (ref "U1") (pin "33") (pinfunction "GPIO27(SAI2_SD_A)_33") (pintype "bidirectional"))
    )
    (net (code "7") (name "/27_GTIN1") (class "Default")
      (node (ref "R54") (pin "2") (pinfunction "2_2") (pintype "passive"))
      (node (ref "U1") (pin "34") (pinfunction "GPIO28(SAI2_FS_B)_34") (pintype "bidirectional"))
    )
    (net (code "8") (name "/29") (class "Default")
      (node (ref "29") (pin "1") (pinfunction "3_1") (pintype "passive"))
      (node (ref "U1") (pin "36") (pinfunction "GPIO30(USB_HS_D_-)_36") (pintype "bidirectional"))
    )
    (net (code "9") (name "/30") (class "Default")
      (node (ref "30") (pin "1") (pinfunction "3_1") (pintype "passive"))
      (node (ref "U1") (pin "37") (pinfunction "GPIO31(USB_HS_D+)_37") (pintype "bidirectional"))
    )
    (net (code "10") (name "/ADC0") (class "Default")
      (node (ref "C16") (pin "2") (pinfunction "2_2") (pintype "passive"))
      (node (ref "IC4") (pin "1") (pinfunction "OUT_1") (pintype "output"))
      (node (ref "R21") (pin "2") (pinfunction "2_2") (pintype "passive"))
      (node (ref "U1") (pin "22") (pinfunction "GPIO16(ADC1_INP10)_22") (pintype "bidirectional"))
    )
    (net (code "11") (name "/ADC1") (class "Default")
      (node (ref "C17") (pin "2") (pinfunction "2_2") (pintype "passive"))
      (node (ref "IC4") (pin "7") (pinfunction "OUT_7") (pintype "output"))
      (node (ref "R25") (pin "2") (pinfunction "2_2") (pintype "passive"))
      (node (ref "U1") (pin "23") (pinfunction "GPIO17(ADC1_INP15)_23") (pintype "bidirectional"))
    )
    (net (code "12") (name "/ADC2") (class "Default")
      (node (ref "C20") (pin "2") (pinfunction "2_2") (pintype "passive"))
      (node (ref "IC4") (pin "8") (pinfunction "OUT_8") (pintype "output"))
      (node (ref "R30") (pin "2") (pinfunction "2_2") (pintype "passive"))
      (node (ref "U1") (pin "24") (pinfunction "GPIO18(ADC1_INP5)_24") (pintype "bidirectional"))
    )
    (net (code "13") (name "/ADC3") (class "Default")
      (node (ref "C21") (pin "2") (pinfunction "2_2") (pintype "passive"))
      (node (ref "IC4") (pin "14") (pinfunction "OUT_14") (pintype "output"))
      (node (ref "R34") (pin "2") (pinfunction "2_2") (pintype "passive"))
      (node (ref "U1") (pin "25") (pinfunction "GPIO19(ADC1_INP7)_25") (pintype "bidirectional"))
    )
    (net (code "14") (name "/ADC4") (class "Default")
      (node (ref "C22") (pin "2") (pinfunction "2_2") (pintype "passive"))
      (node (ref "IC5") (pin "1") (pinfunction "OUT_1") (pintype "output"))
      (node (ref "R38") (pin "2") (pinfunction "2_2") (pintype "passive"))
      (node (ref "U1") (pin "26") (pinfunction "GPIO20(ADC1_INP3)_26") (pintype "bidirectional"))
    )
    (net (code "15") (name "/ADC5") (class "Default")
      (node (ref "C23") (pin "2") (pinfunction "2_2") (pintype "passive"))
      (node (ref "IC5") (pin "7") (pinfunction "OUT_7") (pintype "output"))
      (node (ref "R42") (pin "2") (pinfunction "2_2") (pintype "passive"))
      (node (ref "U1") (pin "27") (pinfunction "GPIO21(ADC1_INP11)_27") (pintype "bidirectional"))
    )
    (net (code "16") (name "/ADC6") (class "Default")
      (node (ref "C24") (pin "2") (pinfunction "2_2") (pintype "passive"))
      (node (ref "IC5") (pin "8") (pinfunction "OUT_8") (pintype "output"))
      (node (ref "R46") (pin "2") (pinfunction "2_2") (pintype "passive"))
      (node (ref "U1") (pin "28") (pinfunction "GPIO22(ADC1_INP4)_28") (pintype "bidirectional"))
    )
    (net (code "17") (name "/ADC7") (class "Default")
      (node (ref "C25") (pin "2") (pinfunction "2_2") (pintype "passive"))
      (node (ref "IC5") (pin "14") (pinfunction "OUT_14") (pintype "output"))
      (node (ref "R50") (pin "2") (pinfunction "2_2") (pintype "passive"))
      (node (ref "U1") (pin "29") (pinfunction "GPIO23(DAC1_OUT2)_29") (pintype "bidirectional"))
    )
    (net (code "18") (name "/ADC8") (class "Default")
      (node (ref "C7") (pin "2") (pinfunction "2_2") (pintype "passive"))
      (node (ref "IC3") (pin "1") (pinfunction "OUT_1") (pintype "output"))
      (node (ref "R8") (pin "2") (pinfunction "2_2") (pintype "passive"))
      (node (ref "U1") (pin "30") (pinfunction "GPIO24(DAC1_OUT1)_30") (pintype "bidirectional"))
    )
    (net (code "19") (name "/ADC9") (class "Default")
      (node (ref "C10") (pin "2") (pinfunction "2_2") (pintype "passive"))
      (node (ref "IC3") (pin "7") (pinfunction "OUT_7") (pintype "output"))
      (node (ref "R15") (pin "2") (pinfunction "2_2") (pintype "passive"))
      (node (ref "U1") (pin "31") (pinfunction "GPIO25(SAI2_MCLK_B)_31") (pintype "bidirectional"))
    )
    (net (code "20") (name "/ADC10") (class "Default")
      (node (ref "C11") (pin "2") (pinfunction "2_2") (pintype "passive"))
      (node (ref "IC3") (pin "8") (pinfunction "OUT_8") (pintype "output"))
      (node (ref "R64") (pin "2") (pinfunction "2_2") (pintype "passive"))
      (node (ref "U1") (pin "32") (pinfunction "GPIO26(SAI2_SD_B)_32") (pintype "bidirectional"))
    )
    (net (code "21") (name "/ADC11") (class "Default")
      (node (ref "C14") (pin "2") (pinfunction "2_2") (pintype "passive"))
      (node (ref "IC3") (pin "14") (pinfunction "OUT_14") (pintype "output"))
      (node (ref "R68") (pin "2") (pinfunction "2_2") (pintype "passive"))
      (node (ref "U1") (pin "35") (pinfunction "GPIO29(SAI2_SCK_B)_35") (pintype "bidirectional"))
    )
    (net (code "22") (name "/AINL") (class "Default")
      (node (ref "R10") (pin "2") (pinfunction "2_2") (pintype "passive"))
      (node (ref "U1") (pin "16") (pinfunction "AUDIO_IN_L_16") (pintype "bidirectional"))
    )
    (net (code "23") (name "/AINR") (class "Default")
      (node (ref "R9") (pin "2") (pinfunction "2_2") (pintype "passive"))
      (node (ref "U1") (pin "17") (pinfunction "AUDIO_IN_R_17") (pintype "bidirectional"))
    )
    (net (code "24") (name "/AOUTL") (class "Default")
      (node (ref "R18") (pin "1") (pinfunction "1_1") (pintype "passive"))
      (node (ref "U1") (pin "18") (pinfunction "AUDIO_OUT_L_18") (pintype "bidirectional"))
    )
    (net (code "25") (name "/AOUTR") (class "Default")
      (node (ref "R17") (pin "1") (pinfunction "1_1") (pintype "passive"))
      (node (ref "U1") (pin "19") (pinfunction "AUDIO_OUT_R_19") (pintype "bidirectional"))
    )
    (net (code "26") (name "5V") (class "Default")
      (node (ref "5V") (pin "1") (pinfunction "3_1") (pintype "passive"))
      (node (ref "C3") (pin "+") (pinfunction "+_+") (pintype "passive"))
      (node (ref "IC2") (pin "3") (pinfunction "VO_3") (pintype "passive"))
      (node (ref "U1") (pin "39") (pinfunction "V_IN_39") (pintype "bidirectional"))
    )
    (net (code "27") (name "GND") (class "Default")
      (node (ref "C1") (pin "-") (pinfunction "-_-") (pintype "passive"))
      (node (ref "C15") (pin "1") (pinfunction "1_1") (pintype "passive"))
      (node (ref "C18") (pin "1") (pinfunction "1_1") (pintype "passive"))
      (node (ref "C2") (pin "+") (pinfunction "+_+") (pintype "passive"))
      (node (ref "C26") (pin "1") (pinfunction "1_1") (pintype "passive"))
      (node (ref "C29") (pin "+") (pinfunction "+_+") (pintype "passive"))
      (node (ref "C3") (pin "-") (pinfunction "-_-") (pintype "passive"))
      (node (ref "C6") (pin "1") (pinfunction "1_1") (pintype "passive"))
      (node (ref "C8") (pin "1") (pinfunction "1_1") (pintype "passive"))
      (node (ref "C9") (pin "2") (pinfunction "2_2") (pintype "passive"))
      (node (ref "GND") (pin "1") (pinfunction "3_1") (pintype "passive"))
      (node (ref "GND2") (pin "1") (pinfunction "3_1") (pintype "passive"))
      (node (ref "GND3") (pin "1") (pinfunction "3_1") (pintype "passive"))
      (node (ref "IC1") (pin "10") (pinfunction "+IN_10") (pintype "input"))
      (node (ref "IC1") (pin "12") (pinfunction "+IN_12") (pintype "input"))
      (node (ref "IC1") (pin "3") (pinfunction "+IN_3") (pintype "input"))
      (node (ref "IC1") (pin "5") (pinfunction "+IN_5") (pintype "input"))
      (node (ref "IC2") (pin "2") (pinfunction "GND_2") (pintype "passive"))
      (node (ref "IC3") (pin "10") (pinfunction "+IN_10") (pintype "input"))
      (node (ref "IC3") (pin "11") (pinfunction "V-_11") (pintype "power_in"))
      (node (ref "IC3") (pin "12") (pinfunction "+IN_12") (pintype "input"))
      (node (ref "IC3") (pin "3") (pinfunction "+IN_3") (pintype "input"))
      (node (ref "IC3") (pin "5") (pinfunction "+IN_5") (pintype "input"))
      (node (ref "IC4") (pin "10") (pinfunction "+IN_10") (pintype "input"))
      (node (ref "IC4") (pin "11") (pinfunction "V-_11") (pintype "power_in"))
      (node (ref "IC4") (pin "12") (pinfunction "+IN_12") (pintype "input"))
      (node (ref "IC4") (pin "3") (pinfunction "+IN_3") (pintype "input"))
      (node (ref "IC4") (pin "5") (pinfunction "+IN_5") (pintype "input"))
      (node (ref "IC5") (pin "10") (pinfunction "+IN_10") (pintype "input"))
      (node (ref "IC5") (pin "11") (pinfunction "V-_11") (pintype "power_in"))
      (node (ref "IC5") (pin "12") (pinfunction "+IN_12") (pintype "input"))
      (node (ref "IC5") (pin "3") (pinfunction "+IN_3") (pintype "input"))
      (node (ref "IC5") (pin "5") (pinfunction "+IN_5") (pintype "input"))
      (node (ref "IC7") (pin "1") (pinfunction "GND_1") (pintype "passive"))
      (node (ref "IC8") (pin "2") (pinfunction "C_2") (pintype "input"))
      (node (ref "Q1") (pin "3") (pinfunction "E_3") (pintype "passive"))
      (node (ref "Q2") (pin "3") (pinfunction "E_3") (pintype "passive"))
      (node (ref "R56") (pin "1") (pinfunction "1_1") (pintype "passive"))
      (node (ref "R60") (pin "1") (pinfunction "1_1") (pintype "passive"))
      (node (ref "U1") (pin "20") (pinfunction "AGND_20") (pintype "bidirectional"))
      (node (ref "U1") (pin "40") (pinfunction "GND_40") (pintype "bidirectional"))
    )
    (net (code "28") (name "Net-(0-3)") (class "Default")
      (node (ref "0") (pin "1") (pinfunction "3_1") (pintype "passive"))
      (node (ref "U1") (pin "1") (pinfunction "GPIO1(USB_HS_ID)_1") (pintype "bidirectional"))
    )
    (net (code "29") (name "Net-(1_SD_D3-3)") (class "Default")
      (node (ref "1_SD_D3") (pin "1") (pinfunction "3_1") (pintype "passive"))
      (node (ref "U1") (pin "2") (pinfunction "GPIO2(SDMMC1_D3)_2") (pintype "bidirectional"))
    )
    (net (code "30") (name "Net-(2_SD_D2-3)") (class "Default")
      (node (ref "2_SD_D2") (pin "1") (pinfunction "3_1") (pintype "passive"))
      (node (ref "U1") (pin "3") (pinfunction "GPIO3(SDMMC1_D2)_3") (pintype "bidirectional"))
    )
    (net (code "31") (name "Net-(3_SD_D1-3)") (class "Default")
      (node (ref "3_SD_D1") (pin "1") (pinfunction "3_1") (pintype "passive"))
      (node (ref "U1") (pin "4") (pinfunction "GPIO4(SDMMC1_D1)_4") (pintype "bidirectional"))
    )
    (net (code "32") (name "Net-(4_SD_D0-3)") (class "Default")
      (node (ref "4_SD_D0") (pin "1") (pinfunction "3_1") (pintype "passive"))
      (node (ref "U1") (pin "5") (pinfunction "GPIO5(SDMMC1_D0)_5") (pintype "bidirectional"))
    )
    (net (code "33") (name "Net-(5_SD_CMD-3)") (class "Default")
      (node (ref "5_SD_CMD") (pin "1") (pinfunction "3_1") (pintype "passive"))
      (node (ref "U1") (pin "6") (pinfunction "GPIO6(SDMMC1_CMD)_6") (pintype "bidirectional"))
    )
    (net (code "34") (name "Net-(6_SD_CLK-3)") (class "Default")
      (node (ref "6_SD_CLK") (pin "1") (pinfunction "3_1") (pintype "passive"))
      (node (ref "U1") (pin "7") (pinfunction "GPIO7(SDMMC1_CK)_7") (pintype "bidirectional"))
    )
    (net (code "35") (name "Net-(7_CS-3)") (class "Default")
      (node (ref "7_CS") (pin "1") (pinfunction "3_1") (pintype "passive"))
      (node (ref "U1") (pin "8") (pinfunction "GPIO8(SPI1_NSS)_8") (pintype "bidirectional"))
    )
    (net (code "36") (name "Net-(8_SCK-3)") (class "Default")
      (node (ref "8_SCK") (pin "1") (pinfunction "3_1") (pintype "passive"))
      (node (ref "U1") (pin "9") (pinfunction "GPIO9(SPI1_SCK)_9") (pintype "bidirectional"))
    )
    (net (code "37") (name "Net-(9_MISO-3)") (class "Default")
      (node (ref "9_MISO") (pin "1") (pinfunction "3_1") (pintype "passive"))
      (node (ref "U1") (pin "10") (pinfunction "GPIO10(SPI1_MISO)_10") (pintype "bidirectional"))
    )
    (net (code "38") (name "Net-(10_MOSI-3)") (class "Default")
      (node (ref "10_MOSI") (pin "1") (pinfunction "3_1") (pintype "passive"))
      (node (ref "U1") (pin "11") (pinfunction "GPIO11(SPI1_MOSI)_11") (pintype "bidirectional"))
    )
    (net (code "39") (name "Net-(11-3)") (class "Default")
      (node (ref "11") (pin "1") (pinfunction "3_1") (pintype "passive"))
      (node (ref "U1") (pin "12") (pinfunction "GPIO12(I2C1_SCL)_12") (pintype "bidirectional"))
    )
    (net (code "40") (name "Net-(12-3)") (class "Default")
      (node (ref "12") (pin "1") (pinfunction "3_1") (pintype "passive"))
      (node (ref "U1") (pin "13") (pinfunction "GPIO13(I2C1_SDA)_13") (pintype "bidirectional"))
    )
    (net (code "41") (name "Net-(13_TX-3)") (class "Default")
      (node (ref "13_TX") (pin "1") (pinfunction "3_1") (pintype "passive"))
      (node (ref "U1") (pin "14") (pinfunction "GPIO14(USART1_TX)_14") (pintype "bidirectional"))
    )
    (net (code "42") (name "Net-(14_RX-3)") (class "Default")
      (node (ref "14_RX") (pin "1") (pinfunction "3_1") (pintype "passive"))
      (node (ref "U1") (pin "15") (pinfunction "GPIO15(USART1_RX)_15") (pintype "bidirectional"))
    )
    (net (code "43") (name "Net-(AINL1-3)") (class "Default")
      (node (ref "AINL1") (pin "1") (pinfunction "3_1") (pintype "passive"))
      (node (ref "R1") (pin "1") (pinfunction "1_1") (pintype "passive"))
    )
    (net (code "44") (name "Net-(AINL2-3)") (class "Default")
      (node (ref "AINL2") (pin "1") (pinfunction "3_1") (pintype "passive"))
      (node (ref "R6") (pin "1") (pinfunction "1_1") (pintype "passive"))
    )
    (net (code "45") (name "Net-(AINR1-3)") (class "Default")
      (node (ref "AINR1") (pin "1") (pinfunction "3_1") (pintype "passive"))
      (node (ref "R2") (pin "1") (pinfunction "1_1") (pintype "passive"))
    )
    (net (code "46") (name "Net-(AINR2-3)") (class "Default")
      (node (ref "AINR2") (pin "1") (pinfunction "3_1") (pintype "passive"))
      (node (ref "R4") (pin "1") (pinfunction "1_1") (pintype "passive"))
    )
    (net (code "47") (name "Net-(AOUTL1-3)") (class "Default")
      (node (ref "AOUTL1") (pin "1") (pinfunction "3_1") (pintype "passive"))
      (node (ref "R20") (pin "2") (pinfunction "2_2") (pintype "passive"))
    )
    (net (code "48") (name "Net-(AOUTR1-3)") (class "Default")
      (node (ref "AOUTR1") (pin "1") (pinfunction "3_1") (pintype "passive"))
      (node (ref "R19") (pin "2") (pinfunction "2_2") (pintype "passive"))
    )
    (net (code "49") (name "Net-(CV1A-3)") (class "Default")
      (node (ref "CV1A") (pin "1") (pinfunction "3_1") (pintype "passive"))
      (node (ref "R22") (pin "1") (pinfunction "1_1") (pintype "passive"))
    )
    (net (code "50") (name "Net-(CV1B-3)") (class "Default")
      (node (ref "CV1B") (pin "1") (pinfunction "3_1") (pintype "passive"))
      (node (ref "R23") (pin "1") (pinfunction "1_1") (pintype "passive"))
    )
    (net (code "51") (name "Net-(CV2A-3)") (class "Default")
      (node (ref "CV2A") (pin "1") (pinfunction "3_1") (pintype "passive"))
      (node (ref "R27") (pin "1") (pinfunction "1_1") (pintype "passive"))
    )
    (net (code "52") (name "Net-(CV2B-3)") (class "Default")
      (node (ref "CV2B") (pin "1") (pinfunction "3_1") (pintype "passive"))
      (node (ref "R28") (pin "1") (pinfunction "1_1") (pintype "passive"))
    )
    (net (code "53") (name "Net-(CV3A-3)") (class "Default")
      (node (ref "CV3A") (pin "1") (pinfunction "3_1") (pintype "passive"))
      (node (ref "R31") (pin "1") (pinfunction "1_1") (pintype "passive"))
    )
    (net (code "54") (name "Net-(CV3B-3)") (class "Default")
      (node (ref "CV3B") (pin "1") (pinfunction "3_1") (pintype "passive"))
      (node (ref "R32") (pin "1") (pinfunction "1_1") (pintype "passive"))
    )
    (net (code "55") (name "Net-(CV4A-3)") (class "Default")
      (node (ref "CV4A") (pin "1") (pinfunction "3_1") (pintype "passive"))
      (node (ref "R35") (pin "1") (pinfunction "1_1") (pintype "passive"))
    )
    (net (code "56") (name "Net-(CV4B-3)") (class "Default")
      (node (ref "CV4B") (pin "1") (pinfunction "3_1") (pintype "passive"))
      (node (ref "R36") (pin "1") (pinfunction "1_1") (pintype "passive"))
    )
    (net (code "57") (name "Net-(CV5A-3)") (class "Default")
      (node (ref "CV5A") (pin "1") (pinfunction "3_1") (pintype "passive"))
      (node (ref "R39") (pin "1") (pinfunction "1_1") (pintype "passive"))
    )
    (net (code "58") (name "Net-(CV5B-3)") (class "Default")
      (node (ref "CV5B") (pin "1") (pinfunction "3_1") (pintype "passive"))
      (node (ref "R40") (pin "1") (pinfunction "1_1") (pintype "passive"))
    )
    (net (code "59") (name "Net-(CV6A-3)") (class "Default")
      (node (ref "CV6A") (pin "1") (pinfunction "3_1") (pintype "passive"))
      (node (ref "R44") (pin "1") (pinfunction "1_1") (pintype "passive"))
    )
    (net (code "60") (name "Net-(CV6B-3)") (class "Default")
      (node (ref "CV6B") (pin "1") (pinfunction "3_1") (pintype "passive"))
      (node (ref "R45") (pin "1") (pinfunction "1_1") (pintype "passive"))
    )
    (net (code "61") (name "Net-(CV7A-3)") (class "Default")
      (node (ref "CV7A") (pin "1") (pinfunction "3_1") (pintype "passive"))
      (node (ref "R47") (pin "1") (pinfunction "1_1") (pintype "passive"))
    )
    (net (code "62") (name "Net-(CV7B-3)") (class "Default")
      (node (ref "CV7B") (pin "1") (pinfunction "3_1") (pintype "passive"))
      (node (ref "R48") (pin "1") (pinfunction "1_1") (pintype "passive"))
    )
    (net (code "63") (name "Net-(CV8A-3)") (class "Default")
      (node (ref "CV8A") (pin "1") (pinfunction "3_1") (pintype "passive"))
      (node (ref "R51") (pin "1") (pinfunction "1_1") (pintype "passive"))
    )
    (net (code "64") (name "Net-(CV8B-3)") (class "Default")
      (node (ref "CV8B") (pin "1") (pinfunction "3_1") (pintype "passive"))
      (node (ref "R52") (pin "1") (pinfunction "1_1") (pintype "passive"))
    )
    (net (code "65") (name "Net-(CV9A-3)") (class "Default")
      (node (ref "CV9A") (pin "1") (pinfunction "3_1") (pintype "passive"))
      (node (ref "R11") (pin "1") (pinfunction "1_1") (pintype "passive"))
    )
    (net (code "66") (name "Net-(CV9B-3)") (class "Default")
      (node (ref "CV9B") (pin "1") (pinfunction "3_1") (pintype "passive"))
      (node (ref "R12") (pin "1") (pinfunction "1_1") (pintype "passive"))
    )
    (net (code "67") (name "Net-(CV10A-3)") (class "Default")
      (node (ref "CV10A") (pin "1") (pinfunction "3_1") (pintype "passive"))
      (node (ref "R62") (pin "1") (pinfunction "1_1") (pintype "passive"))
    )
    (net (code "68") (name "Net-(CV10B-3)") (class "Default")
      (node (ref "CV10B") (pin "1") (pinfunction "3_1") (pintype "passive"))
      (node (ref "R63") (pin "1") (pinfunction "1_1") (pintype "passive"))
    )
    (net (code "69") (name "Net-(CV11A-3)") (class "Default")
      (node (ref "CV11A") (pin "1") (pinfunction "3_1") (pintype "passive"))
      (node (ref "R65") (pin "1") (pinfunction "1_1") (pintype "passive"))
    )
    (net (code "70") (name "Net-(CV11B-3)") (class "Default")
      (node (ref "CV11B") (pin "1") (pinfunction "3_1") (pintype "passive"))
      (node (ref "R66") (pin "1") (pinfunction "1_1") (pintype "passive"))
    )
    (net (code "71") (name "Net-(CV12A-3)") (class "Default")
      (node (ref "CV12A") (pin "1") (pinfunction "3_1") (pintype "passive"))
      (node (ref "R69") (pin "1") (pinfunction "1_1") (pintype "passive"))
    )
    (net (code "72") (name "Net-(CV12B-3)") (class "Default")
      (node (ref "CV12B") (pin "1") (pinfunction "3_1") (pintype "passive"))
      (node (ref "R70") (pin "1") (pinfunction "1_1") (pintype "passive"))
    )
    (net (code "73") (name "Net-(GTIN1-3)") (class "Default")
      (node (ref "GTIN1") (pin "1") (pinfunction "3_1") (pintype "passive"))
      (node (ref "R55") (pin "1") (pinfunction "1_1") (pintype "passive"))
    )
    (net (code "74") (name "Net-(GTIN2-3)") (class "Default")
      (node (ref "GTIN2") (pin "1") (pinfunction "3_1") (pintype "passive"))
      (node (ref "R59") (pin "1") (pinfunction "1_1") (pintype "passive"))
    )
    (net (code "75") (name "Net-(IC1A--IN)") (class "Default")
      (node (ref "C4") (pin "1") (pinfunction "1_1") (pintype "passive"))
      (node (ref "IC1") (pin "2") (pinfunction "-IN_2") (pintype "input"))
      (node (ref "R2") (pin "2") (pinfunction "2_2") (pintype "passive"))
      (node (ref "R3") (pin "1") (pinfunction "1_1") (pintype "passive"))
      (node (ref "R4") (pin "2") (pinfunction "2_2") (pintype "passive"))
    )
    (net (code "76") (name "Net-(IC1A-OUT)") (class "Default")
      (node (ref "C4") (pin "2") (pinfunction "2_2") (pintype "passive"))
      (node (ref "IC1") (pin "1") (pinfunction "OUT_1") (pintype "output"))
      (node (ref "R3") (pin "2") (pinfunction "2_2") (pintype "passive"))
      (node (ref "R9") (pin "1") (pinfunction "1_1") (pintype "passive"))
    )
    (net (code "77") (name "Net-(IC1B--IN)") (class "Default")
      (node (ref "C5") (pin "1") (pinfunction "1_1") (pintype "passive"))
      (node (ref "IC1") (pin "6") (pinfunction "-IN_6") (pintype "input"))
      (node (ref "R1") (pin "2") (pinfunction "2_2") (pintype "passive"))
      (node (ref "R5") (pin "1") (pinfunction "1_1") (pintype "passive"))
      (node (ref "R6") (pin "2") (pinfunction "2_2") (pintype "passive"))
    )
    (net (code "78") (name "Net-(IC1B-OUT)") (class "Default")
      (node (ref "C5") (pin "2") (pinfunction "2_2") (pintype "passive"))
      (node (ref "IC1") (pin "7") (pinfunction "OUT_7") (pintype "output"))
      (node (ref "R10") (pin "1") (pinfunction "1_1") (pintype "passive"))
      (node (ref "R5") (pin "2") (pinfunction "2_2") (pintype "passive"))
    )
    (net (code "79") (name "Net-(IC1C--IN)") (class "Default")
      (node (ref "C12") (pin "1") (pinfunction "1_1") (pintype "passive"))
      (node (ref "IC1") (pin "9") (pinfunction "-IN_9") (pintype "input"))
      (node (ref "R14") (pin "1") (pinfunction "1_1") (pintype "passive"))
      (node (ref "R17") (pin "2") (pinfunction "2_2") (pintype "passive"))
    )
    (net (code "80") (name "Net-(IC1C-OUT)") (class "Default")
      (node (ref "C12") (pin "2") (pinfunction "2_2") (pintype "passive"))
      (node (ref "IC1") (pin "8") (pinfunction "OUT_8") (pintype "output"))
      (node (ref "R14") (pin "2") (pinfunction "2_2") (pintype "passive"))
      (node (ref "R19") (pin "1") (pinfunction "1_1") (pintype "passive"))
    )
    (net (code "81") (name "Net-(IC1D--IN)") (class "Default")
      (node (ref "C13") (pin "1") (pinfunction "1_1") (pintype "passive"))
      (node (ref "IC1") (pin "13") (pinfunction "-IN_13") (pintype "input"))
      (node (ref "R16") (pin "1") (pinfunction "1_1") (pintype "passive"))
      (node (ref "R18") (pin "2") (pinfunction "2_2") (pintype "passive"))
    )
    (net (code "82") (name "Net-(IC1D-OUT)") (class "Default")
      (node (ref "C13") (pin "2") (pinfunction "2_2") (pintype "passive"))
      (node (ref "IC1") (pin "14") (pinfunction "OUT_14") (pintype "output"))
      (node (ref "R16") (pin "2") (pinfunction "2_2") (pintype "passive"))
      (node (ref "R20") (pin "1") (pinfunction "1_1") (pintype "passive"))
    )
    (net (code "83") (name "Net-(IC3A--IN)") (class "Default")
      (node (ref "C7") (pin "1") (pinfunction "1_1") (pintype "passive"))
      (node (ref "IC3") (pin "2") (pinfunction "-IN_2") (pintype "input"))
      (node (ref "R11") (pin "2") (pinfunction "2_2") (pintype "passive"))
      (node (ref "R12") (pin "2") (pinfunction "2_2") (pintype "passive"))
      (node (ref "R13") (pin "2") (pinfunction "2_2") (pintype "passive"))
      (node (ref "R8") (pin "1") (pinfunction "1_1") (pintype "passive"))
    )
    (net (code "84") (name "Net-(IC3B--IN)") (class "Default")
      (node (ref "C10") (pin "1") (pinfunction "1_1") (pintype "passive"))
      (node (ref "IC3") (pin "6") (pinfunction "-IN_6") (pintype "input"))
      (node (ref "R15") (pin "1") (pinfunction "1_1") (pintype "passive"))
      (node (ref "R29") (pin "2") (pinfunction "2_2") (pintype "passive"))
      (node (ref "R62") (pin "2") (pinfunction "2_2") (pintype "passive"))
      (node (ref "R63") (pin "2") (pinfunction "2_2") (pintype "passive"))
    )
    (net (code "85") (name "Net-(IC3C--IN)") (class "Default")
      (node (ref "C11") (pin "1") (pinfunction "1_1") (pintype "passive"))
      (node (ref "IC3") (pin "9") (pinfunction "-IN_9") (pintype "input"))
      (node (ref "R64") (pin "1") (pinfunction "1_1") (pintype "passive"))
      (node (ref "R65") (pin "2") (pinfunction "2_2") (pintype "passive"))
      (node (ref "R66") (pin "2") (pinfunction "2_2") (pintype "passive"))
      (node (ref "R67") (pin "2") (pinfunction "2_2") (pintype "passive"))
    )
    (net (code "86") (name "Net-(IC3D--IN)") (class "Default")
      (node (ref "C14") (pin "1") (pinfunction "1_1") (pintype "passive"))
      (node (ref "IC3") (pin "13") (pinfunction "-IN_13") (pintype "input"))
      (node (ref "R68") (pin "1") (pinfunction "1_1") (pintype "passive"))
      (node (ref "R69") (pin "2") (pinfunction "2_2") (pintype "passive"))
      (node (ref "R70") (pin "2") (pinfunction "2_2") (pintype "passive"))
      (node (ref "R71") (pin "2") (pinfunction "2_2") (pintype "passive"))
    )
    (net (code "87") (name "Net-(IC4A--IN)") (class "Default")
      (node (ref "C16") (pin "1") (pinfunction "1_1") (pintype "passive"))
      (node (ref "IC4") (pin "2") (pinfunction "-IN_2") (pintype "input"))
      (node (ref "R21") (pin "1") (pinfunction "1_1") (pintype "passive"))
      (node (ref "R22") (pin "2") (pinfunction "2_2") (pintype "passive"))
      (node (ref "R23") (pin "2") (pinfunction "2_2") (pintype "passive"))
      (node (ref "R24") (pin "2") (pinfunction "2_2") (pintype "passive"))
    )
    (net (code "88") (name "Net-(IC4B--IN)") (class "Default")
      (node (ref "C17") (pin "1") (pinfunction "1_1") (pintype "passive"))
      (node (ref "IC4") (pin "6") (pinfunction "-IN_6") (pintype "input"))
      (node (ref "R25") (pin "1") (pinfunction "1_1") (pintype "passive"))
      (node (ref "R26") (pin "2") (pinfunction "2_2") (pintype "passive"))
      (node (ref "R27") (pin "2") (pinfunction "2_2") (pintype "passive"))
      (node (ref "R28") (pin "2") (pinfunction "2_2") (pintype "passive"))
    )
    (net (code "89") (name "Net-(IC4C--IN)") (class "Default")
      (node (ref "C20") (pin "1") (pinfunction "1_1") (pintype "passive"))
      (node (ref "IC4") (pin "9") (pinfunction "-IN_9") (pintype "input"))
      (node (ref "R30") (pin "1") (pinfunction "1_1") (pintype "passive"))
      (node (ref "R31") (pin "2") (pinfunction "2_2") (pintype "passive"))
      (node (ref "R32") (pin "2") (pinfunction "2_2") (pintype "passive"))
      (node (ref "R33") (pin "2") (pinfunction "2_2") (pintype "passive"))
    )
    (net (code "90") (name "Net-(IC4D--IN)") (class "Default")
      (node (ref "C21") (pin "1") (pinfunction "1_1") (pintype "passive"))
      (node (ref "IC4") (pin "13") (pinfunction "-IN_13") (pintype "input"))
      (node (ref "R34") (pin "1") (pinfunction "1_1") (pintype "passive"))
      (node (ref "R35") (pin "2") (pinfunction "2_2") (pintype "passive"))
      (node (ref "R36") (pin "2") (pinfunction "2_2") (pintype "passive"))
      (node (ref "R37") (pin "2") (pinfunction "2_2") (pintype "passive"))
    )
    (net (code "91") (name "Net-(IC5A--IN)") (class "Default")
      (node (ref "C22") (pin "1") (pinfunction "1_1") (pintype "passive"))
      (node (ref "IC5") (pin "2") (pinfunction "-IN_2") (pintype "input"))
      (node (ref "R38") (pin "1") (pinfunction "1_1") (pintype "passive"))
      (node (ref "R39") (pin "2") (pinfunction "2_2") (pintype "passive"))
      (node (ref "R40") (pin "2") (pinfunction "2_2") (pintype "passive"))
      (node (ref "R41") (pin "2") (pinfunction "2_2") (pintype "passive"))
    )
    (net (code "92") (name "Net-(IC5B--IN)") (class "Default")
      (node (ref "C23") (pin "1") (pinfunction "1_1") (pintype "passive"))
      (node (ref "IC5") (pin "6") (pinfunction "-IN_6") (pintype "input"))
      (node (ref "R42") (pin "1") (pinfunction "1_1") (pintype "passive"))
      (node (ref "R43") (pin "2") (pinfunction "2_2") (pintype "passive"))
      (node (ref "R44") (pin "2") (pinfunction "2_2") (pintype "passive"))
      (node (ref "R45") (pin "2") (pinfunction "2_2") (pintype "passive"))
    )
    (net (code "93") (name "Net-(IC5C--IN)") (class "Default")
      (node (ref "C24") (pin "1") (pinfunction "1_1") (pintype "passive"))
      (node (ref "IC5") (pin "9") (pinfunction "-IN_9") (pintype "input"))
      (node (ref "R46") (pin "1") (pinfunction "1_1") (pintype "passive"))
      (node (ref "R47") (pin "2") (pinfunction "2_2") (pintype "passive"))
      (node (ref "R48") (pin "2") (pinfunction "2_2") (pintype "passive"))
      (node (ref "R49") (pin "2") (pinfunction "2_2") (pintype "passive"))
    )
    (net (code "94") (name "Net-(IC5D--IN)") (class "Default")
      (node (ref "C25") (pin "1") (pinfunction "1_1") (pintype "passive"))
      (node (ref "IC5") (pin "13") (pinfunction "-IN_13") (pintype "input"))
      (node (ref "R50") (pin "1") (pinfunction "1_1") (pintype "passive"))
      (node (ref "R51") (pin "2") (pinfunction "2_2") (pintype "passive"))
      (node (ref "R52") (pin "2") (pinfunction "2_2") (pintype "passive"))
      (node (ref "R53") (pin "2") (pinfunction "2_2") (pintype "passive"))
    )
    (net (code "95") (name "Net-(Q1-B)") (class "Default")
      (node (ref "Q1") (pin "2") (pinfunction "B_2") (pintype "passive"))
      (node (ref "R55") (pin "2") (pinfunction "2_2") (pintype "passive"))
      (node (ref "R56") (pin "2") (pinfunction "2_2") (pintype "passive"))
    )
    (net (code "96") (name "Net-(Q1-C)") (class "Default")
      (node (ref "Q1") (pin "1") (pinfunction "C_1") (pintype "passive"))
      (node (ref "R54") (pin "1") (pinfunction "1_1") (pintype "passive"))
      (node (ref "R57") (pin "1") (pinfunction "1_1") (pintype "passive"))
    )
    (net (code "97") (name "Net-(Q2-B)") (class "Default")
      (node (ref "Q2") (pin "2") (pinfunction "B_2") (pintype "passive"))
      (node (ref "R59") (pin "2") (pinfunction "2_2") (pintype "passive"))
      (node (ref "R60") (pin "2") (pinfunction "2_2") (pintype "passive"))
    )
    (net (code "98") (name "Net-(Q2-C)") (class "Default")
      (node (ref "Q2") (pin "1") (pinfunction "C_1") (pintype "passive"))
      (node (ref "R58") (pin "1") (pinfunction "1_1") (pintype "passive"))
      (node (ref "R61") (pin "1") (pinfunction "1_1") (pintype "passive"))
    )
  )
)
